# NVME.net
KiCad netlist of a schematic drawn in Altium Designer
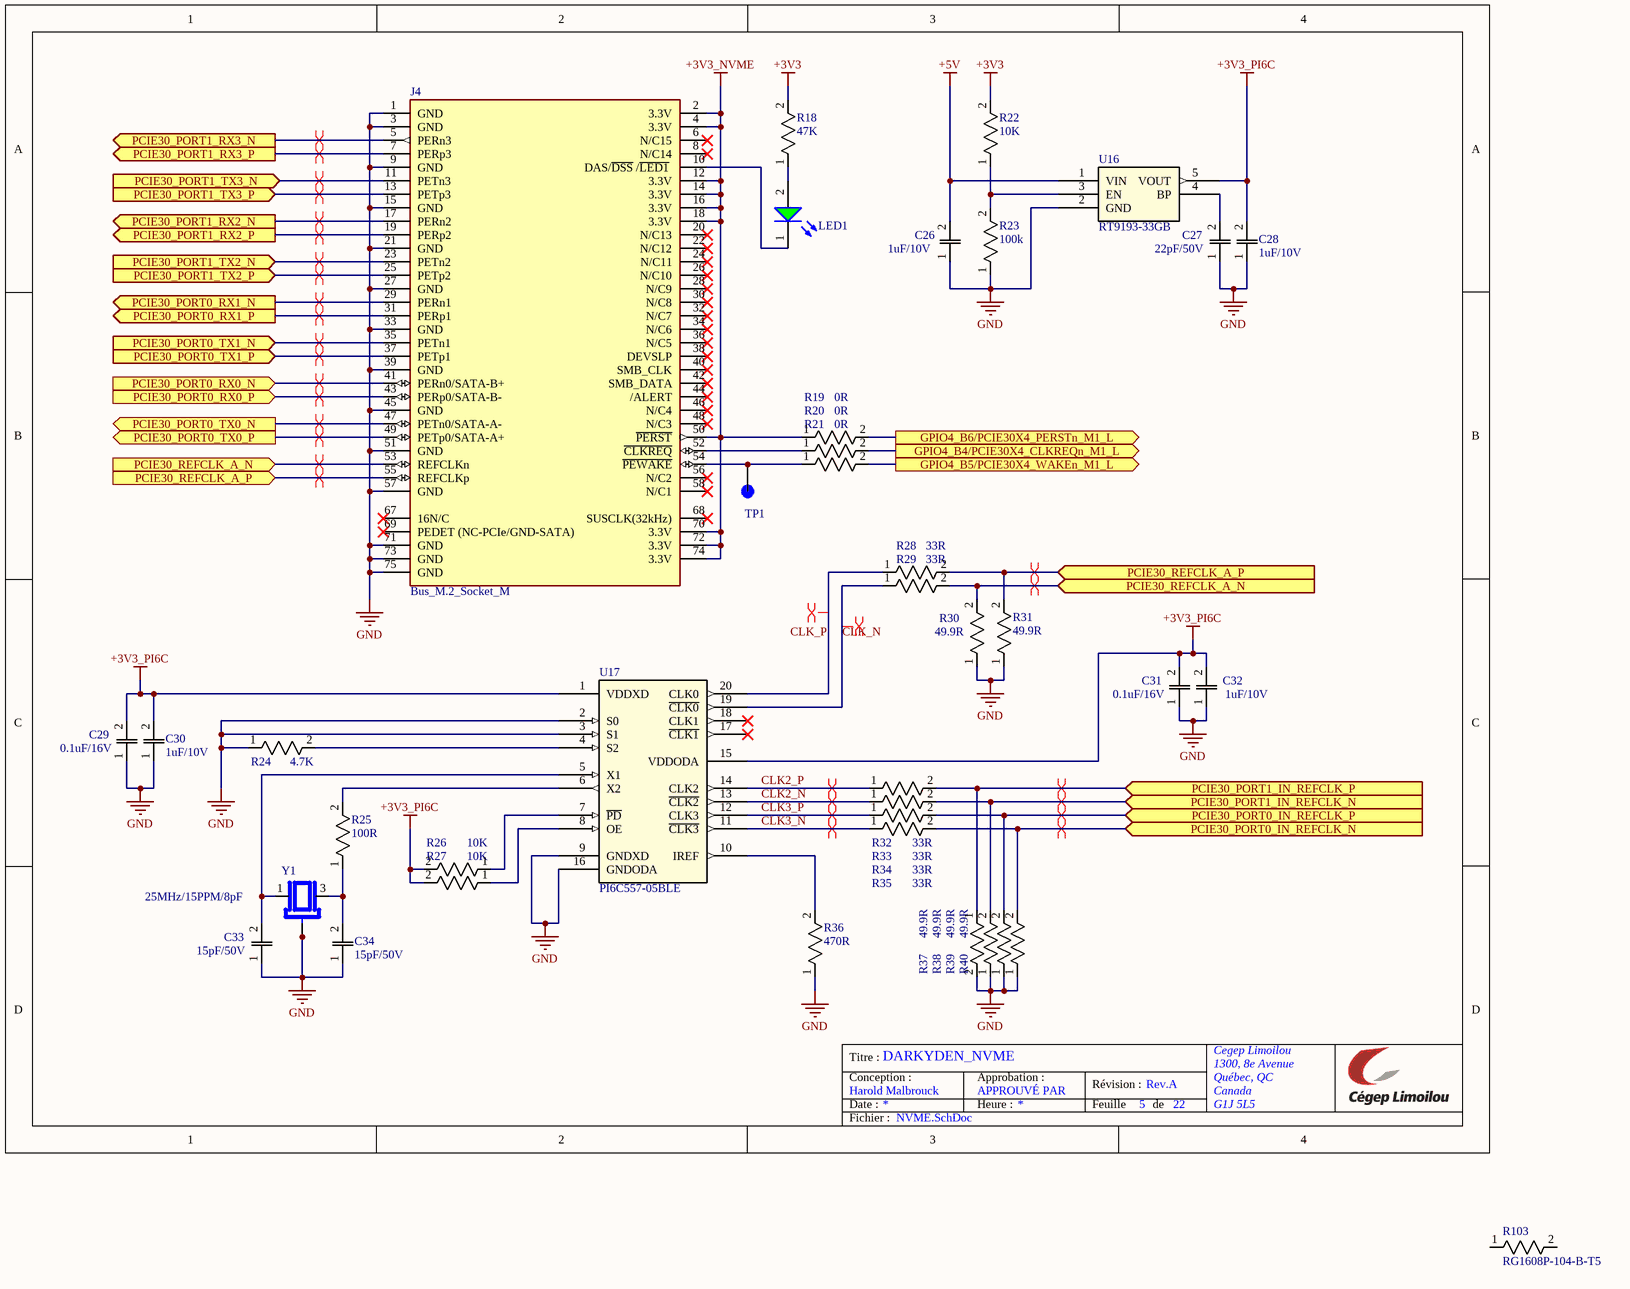
[diagram p0: NVME.SchDoc]

(export (version "E")
  (design (tool "Eeschema 10.0.6"))
  (components
    (comp (ref "C26")
      (value "1uF/10V")
      (footprint "CAPC220145_88N_KEM")
      (description "Multilayer Ceramic Capacitors MLCC - SMD/SMT 10V 1uF X7R 0805 10%")
      (fields
        (field (name "MANUFACTURER") "KEMET")
        (field (name "MANUFACTURER PART NUMBER") "C0805C105K8RACTU")
      )
      (libsource (lib "C0805C105K8RACTU") (part "C0805C105K8RACTU"))
    )
    (comp (ref "C27")
      (value "22pF/50V")
      (footprint "CAPC220145_88N_KEM")
      (description "Cap Ceramic 22pF 50V X7R 5% Pad SMD 0805 125°C T/R")
      (fields
        (field (name "MANUFACTURER") "KEMET")
        (field (name "MANUFACTURER PART NUMBER") "C0805C220J5RACTU")
      )
      (libsource (lib "C0805C220J5RACTU") (part "C0805C220J5RACTU"))
    )
    (comp (ref "C28")
      (value "1uF/10V")
      (footprint "CAPC220145_88N_KEM")
      (description "Multilayer Ceramic Capacitors MLCC - SMD/SMT 10V 1uF X7R 0805 10%")
      (fields
        (field (name "MANUFACTURER") "KEMET")
        (field (name "MANUFACTURER PART NUMBER") "C0805C105K8RACTU")
      )
      (libsource (lib "C0805C105K8RACTU") (part "C0805C105K8RACTU"))
    )
    (comp (ref "C29")
      (value "0.1uF/16V")
      (footprint "CAPC220145_88N_KEM")
      (description "0.1uF/16V ±10% X7R 0805 (2012METRIC) Ceramic Capacitor SMD Auto X7R")
      (fields
        (field (name "MANUFACTURER") "KEMET")
        (field (name "MANUFACTURER PART NUMBER") "C0805C104K4RACAUTO")
      )
      (libsource (lib "C0805C104K4RACAUTO") (part "C0805C104K4RACAUTO"))
    )
    (comp (ref "C30")
      (value "1uF/10V")
      (footprint "CAPC220145_88N_KEM")
      (description "Multilayer Ceramic Capacitors MLCC - SMD/SMT 10V 1uF X7R 0805 10%")
      (fields
        (field (name "MANUFACTURER") "KEMET")
        (field (name "MANUFACTURER PART NUMBER") "C0805C105K8RACTU")
      )
      (libsource (lib "C0805C105K8RACTU") (part "C0805C105K8RACTU"))
    )
    (comp (ref "C31")
      (value "0.1uF/16V")
      (footprint "CAPC220145_88N_KEM")
      (description "0.1uF/16V ±10% X7R 0805 (2012METRIC) Ceramic Capacitor SMD Auto X7R")
      (fields
        (field (name "MANUFACTURER") "KEMET")
        (field (name "MANUFACTURER PART NUMBER") "C0805C104K4RACAUTO")
      )
      (libsource (lib "C0805C104K4RACAUTO") (part "C0805C104K4RACAUTO"))
    )
    (comp (ref "C32")
      (value "1uF/10V")
      (footprint "CAPC220145_88N_KEM")
      (description "Multilayer Ceramic Capacitors MLCC - SMD/SMT 10V 1uF X7R 0805 10%")
      (fields
        (field (name "MANUFACTURER") "KEMET")
        (field (name "MANUFACTURER PART NUMBER") "C0805C105K8RACTU")
      )
      (libsource (lib "C0805C105K8RACTU") (part "C0805C105K8RACTU"))
    )
    (comp (ref "C33")
      (value "15pF/50V")
      (footprint "CAPC220145_88N_KEM")
      (description "Multilayer Ceramic Capacitors MLCC - SMD/SMT 50V 15pF X7R 0805 10% AEC-Q200")
      (fields
        (field (name "MANUFACTURER") "KEMET")
        (field (name "MANUFACTURER PART NUMBER") "C0805C150K5RACAUTO")
      )
      (libsource (lib "C0805C150K5RACAUTO") (part "C0805C150K5RACAUTO"))
    )
    (comp (ref "C34")
      (value "15pF/50V")
      (footprint "CAPC220145_88N_KEM")
      (description "Multilayer Ceramic Capacitors MLCC - SMD/SMT 50V 15pF X7R 0805 10% AEC-Q200")
      (fields
        (field (name "MANUFACTURER") "KEMET")
        (field (name "MANUFACTURER PART NUMBER") "C0805C150K5RACAUTO")
      )
      (libsource (lib "C0805C150K5RACAUTO") (part "C0805C150K5RACAUTO"))
    )
    (comp (ref "J4")
      (value "Bus_M.2_Socket_M")
      (footprint "AMPHENOL_MDT420M03001")
      (fields (field (name "MF") "Amphenol Commercial") (field (name "MP") "MDT420M03001"))
      (libsource (lib "Bus_M.2_Socket_M") (part "Bus_M.2_Socket_M"))
    )
    (comp (ref "LED1")
      (value "Green, 3.2V, 140°")
      (footprint "WL-SMCD_0603")
      (description "WL-SMCD Mono-color Chip LED Diffused, SMT, size 0603, Green, 3.2V, 140°")
      (fields
        (field (name "MANUFACTURER PART NUMBER") "150060GS55040")
        (field (name "MANUFACTURER") "Wurth Elektronik")
      )
      (libsource (lib "0603_LED") (part "GREEN"))
    )
    (comp (ref "R18")
      (value "47K")
      (footprint "RC0603N_PAN")
      (description "Resistor Thick Film 0603 47K Ohm 5% 1/10W 200ppm/C Molded SMD Punched Carrier T/R")
      (fields
        (field (name "MANUFACTURER") "Panasonic")
        (field (name "MANUFACTURER PART NUMBER") "ERJ-3GEYJ473V")
      )
      (libsource (lib "ERJ-3GEYJ473V") (part "ERJ-3GEYJ473V"))
    )
    (comp (ref "R19")
      (value "0R")
      (footprint "SamacSys:ERJ3EKF1000V")
      (description "Zero Ohm Resistor, Jumper, 0603 [1608 Metric], Thick Film, 100 mW, 1 A, Surface Mount")
      (fields
        (field (name "MANUFACTURER_PART_NUMBER") "ERJ-3GEY0R00V")
        (field (name "MOUSER PART NUMBER") "667-ERJ-3GEY0R00V")
      )
      (libsource (lib "SamacSys") (part "ERJ-3GEY0R00V"))
    )
    (comp (ref "R20")
      (value "0R")
      (footprint "SamacSys:ERJ3EKF1000V")
      (description "Zero Ohm Resistor, Jumper, 0603 [1608 Metric], Thick Film, 100 mW, 1 A, Surface Mount")
      (fields
        (field (name "MANUFACTURER_PART_NUMBER") "ERJ-3GEY0R00V")
        (field (name "MOUSER PART NUMBER") "667-ERJ-3GEY0R00V")
      )
      (libsource (lib "SamacSys") (part "ERJ-3GEY0R00V"))
    )
    (comp (ref "R21")
      (value "0R")
      (footprint "SamacSys:ERJ3EKF1000V")
      (description "Zero Ohm Resistor, Jumper, 0603 [1608 Metric], Thick Film, 100 mW, 1 A, Surface Mount")
      (fields
        (field (name "MANUFACTURER_PART_NUMBER") "ERJ-3GEY0R00V")
        (field (name "MOUSER PART NUMBER") "667-ERJ-3GEY0R00V")
      )
      (libsource (lib "SamacSys") (part "ERJ-3GEY0R00V"))
    )
    (comp (ref "R22")
      (value "10K")
      (footprint "SamacSys:ERJ3EKF1000V")
      (description "10K Ohm 5% Res Thick Film 0603  0.1W(1/10W) ±200ppm/C Pad SMD Automotive T/R")
      (fields
        (field (name "MANUFACTURER_PART_NUMBER") "ERJ-3GEYJ103V")
        (field (name "MOUSER PART NUMBER") "667-ERJ-3GEYJ103V")
      )
      (libsource (lib "SamacSys") (part "ERJ-3GEYJ103V"))
    )
    (comp (ref "R23")
      (value "100k")
      (footprint "SamacSys:ERJ3EKF1000V")
      (description "100K Ohm 5%  Res Thick Film 0603 1/10W +/-200ppm/ßC Molded SMD Punched Carrier T/R")
      (fields
        (field (name "MANUFACTURER_PART_NUMBER") "ERJ-3GEYJ104V")
        (field (name "MOUSER PART NUMBER") "667-ERJ-3GEYJ104V")
      )
      (libsource (lib "SamacSys") (part "ERJ-3GEYJ104V"))
    )
    (comp (ref "R24")
      (value "4.7K")
      (footprint "RC0603N_PAN")
      (description "Res Thin Film 0603 4.7K Ohm 0.1% 0.1W ±25ppm/°C Molded SMD Punched Carrier T/R")
      (fields
        (field (name "MANUFACTURER") "Panasonic")
        (field (name "MANUFACTURER PART NUMBER") "ERA-3AEB472V")
      )
      (libsource (lib "ERA-3AEB472V") (part "ERA-3AEB472V"))
    )
    (comp (ref "R25")
      (value "100R")
      (footprint "SamacSys:RESC1608X55N")
      (description "100 Ohm 1% 1/10W 0603 ±100ppm/°C Molded SMD Punched Carrier T/R")
      (fields
        (field (name "MANUFACTURER_PART_NUMBER") "ERJ-3EKF1000V")
        (field (name "MOUSER PART NUMBER") "667-ERJ-3EKF1000V")
      )
      (libsource (lib "SamacSys") (part "ERJ-3EKF1000V"))
    )
    (comp (ref "R26")
      (value "10K")
      (footprint "SamacSys:ERJ3EKF1000V")
      (description "10K Ohm 5% Res Thick Film 0603  0.1W(1/10W) ±200ppm/C Pad SMD Automotive T/R")
      (fields
        (field (name "MANUFACTURER_PART_NUMBER") "ERJ-3GEYJ103V")
        (field (name "MOUSER PART NUMBER") "667-ERJ-3GEYJ103V")
      )
      (libsource (lib "SamacSys") (part "ERJ-3GEYJ103V"))
    )
    (comp (ref "R27")
      (value "10K")
      (footprint "SamacSys:ERJ3EKF1000V")
      (description "10K Ohm 5% Res Thick Film 0603  0.1W(1/10W) ±200ppm/C Pad SMD Automotive T/R")
      (fields
        (field (name "MANUFACTURER_PART_NUMBER") "ERJ-3GEYJ103V")
        (field (name "MOUSER PART NUMBER") "667-ERJ-3GEYJ103V")
      )
      (libsource (lib "SamacSys") (part "ERJ-3GEYJ103V"))
    )
    (comp (ref "R28")
      (value "33R")
      (footprint "RC0603N_PAN")
      (description "Res Thick Film 0603 33 Ohm 1% 0.1W ±100ppm/°C Molded SMD Punched Carrier T/R")
      (fields
        (field (name "MANUFACTURER") "Panasonic")
        (field (name "MANUFACTURER PART NUMBER") "ERJ-3EKF33R0V")
      )
      (libsource (lib "ERJ-3EKF33R0V") (part "ERJ-3EKF33R0V"))
    )
    (comp (ref "R29")
      (value "33R")
      (footprint "RC0603N_PAN")
      (description "Res Thick Film 0603 33 Ohm 1% 0.1W ±100ppm/°C Molded SMD Punched Carrier T/R")
      (fields
        (field (name "MANUFACTURER") "Panasonic")
        (field (name "MANUFACTURER PART NUMBER") "ERJ-3EKF33R0V")
      )
      (libsource (lib "ERJ-3EKF33R0V") (part "ERJ-3EKF33R0V"))
    )
    (comp (ref "R30")
      (value "49.9R")
      (footprint "RC0603N_PAN")
      (description "100Mw Thick Film Resistors 100Ppm/ 1% 49.9 0603 Chip Resistor Surface Mount Rohs")
      (fields
        (field (name "MANUFACTURER") "Panasonic")
        (field (name "MANUFACTURER PART NUMBER") "ERJ-3EKF49R9V")
      )
      (libsource (lib "ERJ-3EKF49R9V") (part "ERJ-3EKF49R9V"))
    )
    (comp (ref "R31")
      (value "49.9R")
      (footprint "RC0603N_PAN")
      (description "100Mw Thick Film Resistors 100Ppm/ 1% 49.9 0603 Chip Resistor Surface Mount Rohs")
      (fields
        (field (name "MANUFACTURER") "Panasonic")
        (field (name "MANUFACTURER PART NUMBER") "ERJ-3EKF49R9V")
      )
      (libsource (lib "ERJ-3EKF49R9V") (part "ERJ-3EKF49R9V"))
    )
    (comp (ref "R32")
      (value "33R")
      (footprint "RC0603N_PAN")
      (description "Res Thick Film 0603 33 Ohm 1% 0.1W ±100ppm/°C Molded SMD Punched Carrier T/R")
      (fields
        (field (name "MANUFACTURER") "Panasonic")
        (field (name "MANUFACTURER PART NUMBER") "ERJ-3EKF33R0V")
      )
      (libsource (lib "ERJ-3EKF33R0V") (part "ERJ-3EKF33R0V"))
    )
    (comp (ref "R33")
      (value "33R")
      (footprint "RC0603N_PAN")
      (description "Res Thick Film 0603 33 Ohm 1% 0.1W ±100ppm/°C Molded SMD Punched Carrier T/R")
      (fields
        (field (name "MANUFACTURER") "Panasonic")
        (field (name "MANUFACTURER PART NUMBER") "ERJ-3EKF33R0V")
      )
      (libsource (lib "ERJ-3EKF33R0V") (part "ERJ-3EKF33R0V"))
    )
    (comp (ref "R34")
      (value "33R")
      (footprint "RC0603N_PAN")
      (description "Res Thick Film 0603 33 Ohm 1% 0.1W ±100ppm/°C Molded SMD Punched Carrier T/R")
      (fields
        (field (name "MANUFACTURER") "Panasonic")
        (field (name "MANUFACTURER PART NUMBER") "ERJ-3EKF33R0V")
      )
      (libsource (lib "ERJ-3EKF33R0V") (part "ERJ-3EKF33R0V"))
    )
    (comp (ref "R35")
      (value "33R")
      (footprint "RC0603N_PAN")
      (description "Res Thick Film 0603 33 Ohm 1% 0.1W ±100ppm/°C Molded SMD Punched Carrier T/R")
      (fields
        (field (name "MANUFACTURER") "Panasonic")
        (field (name "MANUFACTURER PART NUMBER") "ERJ-3EKF33R0V")
      )
      (libsource (lib "ERJ-3EKF33R0V") (part "ERJ-3EKF33R0V"))
    )
    (comp (ref "R36")
      (value "470R")
      (footprint "RC0603N_PAN")
      (description "Res Thick Film 0603 470 Ohm 5% 1/10W +/-200ppm/ßC Molded SMD Punched Carrier T/R")
      (fields
        (field (name "MANUFACTURER") "Panasonic")
        (field (name "MANUFACTURER PART NUMBER") "ERJ-3GEYJ471V")
      )
      (libsource (lib "ERJ-3GEYJ471V") (part "ERJ-3GEYJ471V"))
    )
    (comp (ref "R37")
      (value "49.9R")
      (footprint "RC0603N_PAN")
      (description "100Mw Thick Film Resistors 100Ppm/ 1% 49.9 0603 Chip Resistor Surface Mount Rohs")
      (fields
        (field (name "MANUFACTURER") "Panasonic")
        (field (name "MANUFACTURER PART NUMBER") "ERJ-3EKF49R9V")
      )
      (libsource (lib "ERJ-3EKF49R9V") (part "ERJ-3EKF49R9V"))
    )
    (comp (ref "R38")
      (value "49.9R")
      (footprint "RC0603N_PAN")
      (description "100Mw Thick Film Resistors 100Ppm/ 1% 49.9 0603 Chip Resistor Surface Mount Rohs")
      (fields
        (field (name "MANUFACTURER") "Panasonic")
        (field (name "MANUFACTURER PART NUMBER") "ERJ-3EKF49R9V")
      )
      (libsource (lib "ERJ-3EKF49R9V") (part "ERJ-3EKF49R9V"))
    )
    (comp (ref "R39")
      (value "49.9R")
      (footprint "RC0603N_PAN")
      (description "100Mw Thick Film Resistors 100Ppm/ 1% 49.9 0603 Chip Resistor Surface Mount Rohs")
      (fields
        (field (name "MANUFACTURER") "Panasonic")
        (field (name "MANUFACTURER PART NUMBER") "ERJ-3EKF49R9V")
      )
      (libsource (lib "ERJ-3EKF49R9V") (part "ERJ-3EKF49R9V"))
    )
    (comp (ref "R40")
      (value "49.9R")
      (footprint "RC0603N_PAN")
      (description "100Mw Thick Film Resistors 100Ppm/ 1% 49.9 0603 Chip Resistor Surface Mount Rohs")
      (fields
        (field (name "MANUFACTURER") "Panasonic")
        (field (name "MANUFACTURER PART NUMBER") "ERJ-3EKF49R9V")
      )
      (libsource (lib "ERJ-3EKF49R9V") (part "ERJ-3EKF49R9V"))
    )
    (comp (ref "R103")
      (value "RG1608P-104-B-T5")
      (footprint "RES_0816_SUS")
      (description "No Description Available")
      (libsource (lib "RES_SMD_0603") (part "RG1608P-104-B-T5"))
    )
    (comp (ref "TP1")
      (value "5006")
      (footprint "KEYSTONE_5006")
      (description "Test Point Compact THM PC .350 L .125 OD Heat Resistant Nylon 46 Black ¦ Keystone Electronics 5006")
      (fields (field (name "MF") "Keystone Electronics Corp."))
      (libsource (lib "test_point") (part "5006"))
    )
    (comp (ref "U16")
      (value "RT9193-33GB")
      (footprint "SOT-23-5_RIT")
      (description "RT9193 Series 300 mA 3.3 V Ultra-Low Noise Ultra-Fast CMOS LDO Regulator-SC-70-5")
      (fields (field (name "MANUFACTURER") "Richtek"))
      (libsource (lib "RT9193-33GB") (part "RT9193-33GB"))
    )
    (comp (ref "U17")
      (value "PI6C557-05BLE")
      (footprint "L20_PER-M")
      (description "Clock Generators & Support Products PCI express Gen 2 4 output clock gen")
      (fields (field (name "MANUFACTURER") "Diodes"))
      (libsource (lib "PI6C557-05BLE") (part "PI6C557-05BLE"))
    )
    (comp (ref "Y1")
      (value "25MHz/15PPM/8pF")
      (footprint "XTAL_ECS-250-8-37B2-RWY-TR")
      (description "Crystal 25MHz ±15ppm (Tol) ±15ppm (Stability) 8pF FUND 50Ohm 4-Pin Mini-CSMD T/R")
      (fields (field (name "MF") "{'manufacturer': u'ECS Inc.'}") (field (name "MP") "ECS-250-8-37B2-RWY-TR"))
      (libsource (lib "ECS-250-8-37B2-RWY-TR") (part "ECS-250-8-37B2-RWY-TR"))
    )
  )
  (nets
    (net (code "1") (name "+3V3") (class "Default")
      (node (ref "R18") (pin "2") (pinfunction "2_2") (pintype "passive"))
      (node (ref "R22") (pin "2") (pinfunction "2_2") (pintype "passive"))
    )
    (net (code "2") (name "+3V3_NVME") (class "Default")
      (node (ref "J4") (pin "12") (pinfunction "3.3V_12") (pintype "power_in"))
      (node (ref "J4") (pin "14") (pinfunction "3.3V_14") (pintype "power_in"))
      (node (ref "J4") (pin "16") (pinfunction "3.3V_16") (pintype "power_in"))
      (node (ref "J4") (pin "18") (pinfunction "3.3V_18") (pintype "power_in"))
      (node (ref "J4") (pin "2") (pinfunction "3.3V_2") (pintype "power_in"))
      (node (ref "J4") (pin "4") (pinfunction "3.3V_4") (pintype "power_in"))
      (node (ref "J4") (pin "50") (pinfunction "~{PERST}_50") (pintype "output"))
      (node (ref "J4") (pin "70") (pinfunction "3.3V_70") (pintype "power_in"))
      (node (ref "J4") (pin "72") (pinfunction "3.3V_72") (pintype "power_in"))
      (node (ref "J4") (pin "74") (pinfunction "3.3V_74") (pintype "power_in"))
      (node (ref "R19") (pin "1") (pinfunction "1_1") (pintype "passive"))
    )
    (net (code "3") (name "+3V3_PI6C") (class "Default")
      (node (ref "C28") (pin "2") (pinfunction "2_2") (pintype "passive"))
      (node (ref "C29") (pin "2") (pinfunction "2_2") (pintype "passive"))
      (node (ref "C30") (pin "2") (pinfunction "2_2") (pintype "passive"))
      (node (ref "C31") (pin "2") (pinfunction "2_2") (pintype "passive"))
      (node (ref "C32") (pin "2") (pinfunction "2_2") (pintype "passive"))
      (node (ref "R26") (pin "2") (pinfunction "2_2") (pintype "passive"))
      (node (ref "R27") (pin "2") (pinfunction "2_2") (pintype "passive"))
      (node (ref "U16") (pin "5") (pinfunction "VOUT_5") (pintype "output"))
      (node (ref "U17") (pin "1") (pinfunction "VDDXD_1") (pintype "power_in"))
      (node (ref "U17") (pin "15") (pinfunction "VDDODA_15") (pintype "power_in"))
    )
    (net (code "4") (name "+5V") (class "Default")
      (node (ref "C26") (pin "2") (pinfunction "2_2") (pintype "passive"))
      (node (ref "U16") (pin "1") (pinfunction "VIN_1") (pintype "power_in"))
    )
    (net (code "5") (name "/CLK2_N") (class "Default")
      (node (ref "R33") (pin "1") (pinfunction "1_1") (pintype "passive"))
      (node (ref "U17") (pin "13") (pinfunction "~{CLK2}_13") (pintype "output"))
    )
    (net (code "6") (name "/CLK2_P") (class "Default")
      (node (ref "R32") (pin "1") (pinfunction "1_1") (pintype "passive"))
      (node (ref "U17") (pin "14") (pinfunction "CLK2_14") (pintype "output"))
    )
    (net (code "7") (name "/CLK3_N") (class "Default")
      (node (ref "R35") (pin "1") (pinfunction "1_1") (pintype "passive"))
      (node (ref "U17") (pin "11") (pinfunction "~{CLK3}_11") (pintype "output"))
    )
    (net (code "8") (name "/CLK3_P") (class "Default")
      (node (ref "R34") (pin "1") (pinfunction "1_1") (pintype "passive"))
      (node (ref "U17") (pin "12") (pinfunction "CLK3_12") (pintype "output"))
    )
    (net (code "9") (name "/CLK_N") (class "Default")
      (node (ref "R29") (pin "1") (pinfunction "1_1") (pintype "passive"))
      (node (ref "U17") (pin "19") (pinfunction "~{CLK0}_19") (pintype "output"))
    )
    (net (code "10") (name "/CLK_P") (class "Default")
      (node (ref "R28") (pin "1") (pinfunction "1_1") (pintype "passive"))
      (node (ref "U17") (pin "20") (pinfunction "CLK0_20") (pintype "output"))
    )
    (net (code "11") (name "/GPIO4_B4{slash}PCIE30X4_CLKREQn_M1_L") (class "Default")
      (node (ref "R20") (pin "2") (pinfunction "2_2") (pintype "passive"))
    )
    (net (code "12") (name "/GPIO4_B5{slash}PCIE30X4_WAKEn_M1_L") (class "Default")
      (node (ref "R21") (pin "2") (pinfunction "2_2") (pintype "passive"))
    )
    (net (code "13") (name "/GPIO4_B6{slash}PCIE30X4_PERSTn_M1_L") (class "Default")
      (node (ref "R19") (pin "2") (pinfunction "2_2") (pintype "passive"))
    )
    (net (code "14") (name "/PCIE30_PORT0_IN_REFCLK_N") (class "Default")
      (node (ref "R35") (pin "2") (pinfunction "2_2") (pintype "passive"))
      (node (ref "R40") (pin "2") (pinfunction "2_2") (pintype "passive"))
    )
    (net (code "15") (name "/PCIE30_PORT0_IN_REFCLK_P") (class "Default")
      (node (ref "R34") (pin "2") (pinfunction "2_2") (pintype "passive"))
      (node (ref "R39") (pin "2") (pinfunction "2_2") (pintype "passive"))
    )
    (net (code "16") (name "/PCIE30_PORT0_RX0_N") (class "Default")
      (node (ref "J4") (pin "41") (pinfunction "PERn0/SATA-B+_41") (pintype "bidirectional"))
    )
    (net (code "17") (name "/PCIE30_PORT0_RX0_P") (class "Default")
      (node (ref "J4") (pin "43") (pinfunction "PERp0/SATA-B-_43") (pintype "bidirectional"))
    )
    (net (code "18") (name "/PCIE30_PORT0_RX1_N") (class "Default")
      (node (ref "J4") (pin "29") (pinfunction "PERn1_29") (pintype "passive"))
    )
    (net (code "19") (name "/PCIE30_PORT0_RX1_P") (class "Default")
      (node (ref "J4") (pin "31") (pinfunction "PERp1_31") (pintype "passive"))
    )
    (net (code "20") (name "/PCIE30_PORT0_TX0_N") (class "Default")
      (node (ref "J4") (pin "47") (pinfunction "PETn0/SATA-A-_47") (pintype "bidirectional"))
    )
    (net (code "21") (name "/PCIE30_PORT0_TX0_P") (class "Default")
      (node (ref "J4") (pin "49") (pinfunction "PETp0/SATA-A+_49") (pintype "bidirectional"))
    )
    (net (code "22") (name "/PCIE30_PORT0_TX1_N") (class "Default")
      (node (ref "J4") (pin "35") (pinfunction "PETn1_35") (pintype "passive"))
    )
    (net (code "23") (name "/PCIE30_PORT0_TX1_P") (class "Default")
      (node (ref "J4") (pin "37") (pinfunction "PETp1_37") (pintype "passive"))
    )
    (net (code "24") (name "/PCIE30_PORT1_IN_REFCLK_N") (class "Default")
      (node (ref "R33") (pin "2") (pinfunction "2_2") (pintype "passive"))
      (node (ref "R38") (pin "2") (pinfunction "2_2") (pintype "passive"))
    )
    (net (code "25") (name "/PCIE30_PORT1_IN_REFCLK_P") (class "Default")
      (node (ref "R32") (pin "2") (pinfunction "2_2") (pintype "passive"))
      (node (ref "R37") (pin "1") (pinfunction "1_1") (pintype "passive"))
    )
    (net (code "26") (name "/PCIE30_PORT1_RX2_N") (class "Default")
      (node (ref "J4") (pin "17") (pinfunction "PERn2_17") (pintype "passive"))
    )
    (net (code "27") (name "/PCIE30_PORT1_RX2_P") (class "Default")
      (node (ref "J4") (pin "19") (pinfunction "PERp2_19") (pintype "passive"))
    )
    (net (code "28") (name "/PCIE30_PORT1_RX3_N") (class "Default")
      (node (ref "J4") (pin "5") (pinfunction "PERn3_5") (pintype "output"))
    )
    (net (code "29") (name "/PCIE30_PORT1_RX3_P") (class "Default")
      (node (ref "J4") (pin "7") (pinfunction "PERp3_7") (pintype "passive"))
    )
    (net (code "30") (name "/PCIE30_PORT1_TX2_N") (class "Default")
      (node (ref "J4") (pin "23") (pinfunction "PETn2_23") (pintype "passive"))
    )
    (net (code "31") (name "/PCIE30_PORT1_TX2_P") (class "Default")
      (node (ref "J4") (pin "25") (pinfunction "PETp2_25") (pintype "passive"))
    )
    (net (code "32") (name "/PCIE30_PORT1_TX3_N") (class "Default")
      (node (ref "J4") (pin "11") (pinfunction "PETn3_11") (pintype "passive"))
    )
    (net (code "33") (name "/PCIE30_PORT1_TX3_P") (class "Default")
      (node (ref "J4") (pin "13") (pinfunction "PETp3_13") (pintype "passive"))
    )
    (net (code "34") (name "/PCIE30_REFCLK_A_N") (class "Default")
      (node (ref "J4") (pin "53") (pinfunction "REFCLKn_53") (pintype "bidirectional"))
      (node (ref "R29") (pin "2") (pinfunction "2_2") (pintype "passive"))
      (node (ref "R30") (pin "2") (pinfunction "2_2") (pintype "passive"))
    )
    (net (code "35") (name "/PCIE30_REFCLK_A_P") (class "Default")
      (node (ref "J4") (pin "55") (pinfunction "REFCLKp_55") (pintype "bidirectional"))
      (node (ref "R28") (pin "2") (pinfunction "2_2") (pintype "passive"))
      (node (ref "R31") (pin "2") (pinfunction "2_2") (pintype "passive"))
    )
    (net (code "36") (name "GND") (class "Default")
      (node (ref "C26") (pin "1") (pinfunction "1_1") (pintype "passive"))
      (node (ref "C27") (pin "1") (pinfunction "1_1") (pintype "passive"))
      (node (ref "C28") (pin "1") (pinfunction "1_1") (pintype "passive"))
      (node (ref "C29") (pin "1") (pinfunction "1_1") (pintype "passive"))
      (node (ref "C30") (pin "1") (pinfunction "1_1") (pintype "passive"))
      (node (ref "C31") (pin "1") (pinfunction "1_1") (pintype "passive"))
      (node (ref "C32") (pin "1") (pinfunction "1_1") (pintype "passive"))
      (node (ref "C33") (pin "1") (pinfunction "1_1") (pintype "passive"))
      (node (ref "C34") (pin "1") (pinfunction "1_1") (pintype "passive"))
      (node (ref "J4") (pin "1") (pinfunction "GND_1") (pintype "passive"))
      (node (ref "J4") (pin "15") (pinfunction "GND_15") (pintype "passive"))
      (node (ref "J4") (pin "21") (pinfunction "GND_21") (pintype "passive"))
      (node (ref "J4") (pin "27") (pinfunction "GND_27") (pintype "passive"))
      (node (ref "J4") (pin "3") (pinfunction "GND_3") (pintype "passive"))
      (node (ref "J4") (pin "33") (pinfunction "GND_33") (pintype "passive"))
      (node (ref "J4") (pin "39") (pinfunction "GND_39") (pintype "passive"))
      (node (ref "J4") (pin "45") (pinfunction "GND_45") (pintype "passive"))
      (node (ref "J4") (pin "51") (pinfunction "GND_51") (pintype "passive"))
      (node (ref "J4") (pin "57") (pinfunction "GND_57") (pintype "passive"))
      (node (ref "J4") (pin "71") (pinfunction "GND_71") (pintype "passive"))
      (node (ref "J4") (pin "73") (pinfunction "GND_73") (pintype "passive"))
      (node (ref "J4") (pin "75") (pinfunction "GND_75") (pintype "passive"))
      (node (ref "J4") (pin "9") (pinfunction "GND_9") (pintype "passive"))
      (node (ref "R23") (pin "1") (pinfunction "1_1") (pintype "passive"))
      (node (ref "R24") (pin "1") (pinfunction "1_1") (pintype "passive"))
      (node (ref "R30") (pin "1") (pinfunction "1_1") (pintype "passive"))
      (node (ref "R31") (pin "1") (pinfunction "1_1") (pintype "passive"))
      (node (ref "R36") (pin "1") (pinfunction "1_1") (pintype "passive"))
      (node (ref "R37") (pin "2") (pinfunction "2_2") (pintype "passive"))
      (node (ref "R38") (pin "1") (pinfunction "1_1") (pintype "passive"))
      (node (ref "R39") (pin "1") (pinfunction "1_1") (pintype "passive"))
      (node (ref "R40") (pin "1") (pinfunction "1_1") (pintype "passive"))
      (node (ref "U16") (pin "2") (pinfunction "GND_2") (pintype "passive"))
      (node (ref "U17") (pin "16") (pinfunction "GNDODA_16") (pintype "passive"))
      (node (ref "U17") (pin "2") (pinfunction "S0_2") (pintype "input"))
      (node (ref "U17") (pin "3") (pinfunction "S1_3") (pintype "input"))
      (node (ref "U17") (pin "9") (pinfunction "GNDXD_9") (pintype "passive"))
      (node (ref "Y1") (pin "2") (pinfunction "GND_2") (pintype "power_in"))
      (node (ref "Y1") (pin "4") (pinfunction "GND_4") (pintype "power_in"))
    )
    (net (code "37") (name "Net-(J4-DAS{slash}~{DSS}_{slash}~{LED1})") (class "Default")
      (node (ref "J4") (pin "10") (pinfunction "DAS/~{DSS}_/~{LED1}_10") (pintype "passive"))
      (node (ref "LED1") (pin "1") (pinfunction "K_1") (pintype "passive"))
    )
    (net (code "38") (name "Net-(J4-~{CLKREQ})") (class "Default")
      (node (ref "J4") (pin "52") (pinfunction "~{CLKREQ}_52") (pintype "bidirectional"))
      (node (ref "R20") (pin "1") (pinfunction "1_1") (pintype "passive"))
    )
    (net (code "39") (name "Net-(J4-~{PEWAKE})") (class "Default")
      (node (ref "J4") (pin "54") (pinfunction "~{PEWAKE}_54") (pintype "bidirectional"))
      (node (ref "R21") (pin "1") (pinfunction "1_1") (pintype "passive"))
      (node (ref "TP1") (pin "TP") (pinfunction "TP_TP") (pintype "passive"))
    )
    (net (code "40") (name "Net-(LED1-A)") (class "Default")
      (node (ref "LED1") (pin "2") (pinfunction "A_2") (pintype "passive"))
      (node (ref "R18") (pin "1") (pinfunction "1_1") (pintype "passive"))
    )
    (net (code "41") (name "Net-(U16-BP)") (class "Default")
      (node (ref "C27") (pin "2") (pinfunction "2_2") (pintype "passive"))
      (node (ref "U16") (pin "4") (pinfunction "BP_4") (pintype "passive"))
    )
    (net (code "42") (name "Net-(U16-EN)") (class "Default")
      (node (ref "R22") (pin "1") (pinfunction "1_1") (pintype "passive"))
      (node (ref "R23") (pin "2") (pinfunction "2_2") (pintype "passive"))
      (node (ref "U16") (pin "3") (pinfunction "EN_3") (pintype "passive"))
    )
    (net (code "43") (name "Net-(U17-IREF)") (class "Default")
      (node (ref "R36") (pin "2") (pinfunction "2_2") (pintype "passive"))
      (node (ref "U17") (pin "10") (pinfunction "IREF_10") (pintype "output"))
    )
    (net (code "44") (name "Net-(U17-OE)") (class "Default")
      (node (ref "R27") (pin "1") (pinfunction "1_1") (pintype "passive"))
      (node (ref "U17") (pin "8") (pinfunction "OE_8") (pintype "input"))
    )
    (net (code "45") (name "Net-(U17-S2)") (class "Default")
      (node (ref "R24") (pin "2") (pinfunction "2_2") (pintype "passive"))
      (node (ref "U17") (pin "4") (pinfunction "S2_4") (pintype "input"))
    )
    (net (code "46") (name "Net-(U17-X1)") (class "Default")
      (node (ref "C33") (pin "2") (pinfunction "2_2") (pintype "passive"))
      (node (ref "U17") (pin "5") (pinfunction "X1_5") (pintype "input"))
      (node (ref "Y1") (pin "1") (pinfunction "IN/OUT_1") (pintype "passive"))
    )
    (net (code "47") (name "Net-(U17-X2)") (class "Default")
      (node (ref "R25") (pin "2") (pinfunction "2_2") (pintype "passive"))
      (node (ref "U17") (pin "6") (pinfunction "X2_6") (pintype "output"))
    )
    (net (code "48") (name "Net-(U17-~{PD})") (class "Default")
      (node (ref "R26") (pin "1") (pinfunction "1_1") (pintype "passive"))
      (node (ref "U17") (pin "7") (pinfunction "~{PD}_7") (pintype "input"))
    )
    (net (code "49") (name "Net-(Y1-OUT{slash}IN)") (class "Default")
      (node (ref "C34") (pin "2") (pinfunction "2_2") (pintype "passive"))
      (node (ref "R25") (pin "1") (pinfunction "1_1") (pintype "passive"))
      (node (ref "Y1") (pin "3") (pinfunction "OUT/IN_3") (pintype "passive"))
    )
    (net (code "50") (name "unconnected-(J4-16N{slash}C-Pad67)") (class "Default")
      (node (ref "J4") (pin "67") (pinfunction "16N/C_67") (pintype "passive+no_connect"))
    )
    (net (code "51") (name "unconnected-(J4-DEVSLP-Pad38)") (class "Default")
      (node (ref "J4") (pin "38") (pinfunction "DEVSLP_38") (pintype "passive+no_connect"))
    )
    (net (code "52") (name "unconnected-(J4-N{slash}C1-Pad58)") (class "Default")
      (node (ref "J4") (pin "58") (pinfunction "N/C1_58") (pintype "passive+no_connect"))
    )
    (net (code "53") (name "unconnected-(J4-N{slash}C2-Pad56)") (class "Default")
      (node (ref "J4") (pin "56") (pinfunction "N/C2_56") (pintype "passive+no_connect"))
    )
    (net (code "54") (name "unconnected-(J4-N{slash}C3-Pad48)") (class "Default")
      (node (ref "J4") (pin "48") (pinfunction "N/C3_48") (pintype "passive+no_connect"))
    )
    (net (code "55") (name "unconnected-(J4-N{slash}C4-Pad46)") (class "Default")
      (node (ref "J4") (pin "46") (pinfunction "N/C4_46") (pintype "passive+no_connect"))
    )
    (net (code "56") (name "unconnected-(J4-N{slash}C5-Pad36)") (class "Default")
      (node (ref "J4") (pin "36") (pinfunction "N/C5_36") (pintype "passive+no_connect"))
    )
    (net (code "57") (name "unconnected-(J4-N{slash}C6-Pad34)") (class "Default")
      (node (ref "J4") (pin "34") (pinfunction "N/C6_34") (pintype "passive+no_connect"))
    )
    (net (code "58") (name "unconnected-(J4-N{slash}C7-Pad32)") (class "Default")
      (node (ref "J4") (pin "32") (pinfunction "N/C7_32") (pintype "passive+no_connect"))
    )
    (net (code "59") (name "unconnected-(J4-N{slash}C8-Pad30)") (class "Default")
      (node (ref "J4") (pin "30") (pinfunction "N/C8_30") (pintype "passive+no_connect"))
    )
    (net (code "60") (name "unconnected-(J4-N{slash}C9-Pad28)") (class "Default")
      (node (ref "J4") (pin "28") (pinfunction "N/C9_28") (pintype "passive+no_connect"))
    )
    (net (code "61") (name "unconnected-(J4-N{slash}C10-Pad26)") (class "Default")
      (node (ref "J4") (pin "26") (pinfunction "N/C10_26") (pintype "passive+no_connect"))
    )
    (net (code "62") (name "unconnected-(J4-N{slash}C11-Pad24)") (class "Default")
      (node (ref "J4") (pin "24") (pinfunction "N/C11_24") (pintype "passive+no_connect"))
    )
    (net (code "63") (name "unconnected-(J4-N{slash}C12-Pad22)") (class "Default")
      (node (ref "J4") (pin "22") (pinfunction "N/C12_22") (pintype "passive+no_connect"))
    )
    (net (code "64") (name "unconnected-(J4-N{slash}C13-Pad20)") (class "Default")
      (node (ref "J4") (pin "20") (pinfunction "N/C13_20") (pintype "passive+no_connect"))
    )
    (net (code "65") (name "unconnected-(J4-N{slash}C14-Pad8)") (class "Default")
      (node (ref "J4") (pin "8") (pinfunction "N/C14_8") (pintype "passive+no_connect"))
    )
    (net (code "66") (name "unconnected-(J4-N{slash}C15-Pad6)") (class "Default")
      (node (ref "J4") (pin "6") (pinfunction "N/C15_6") (pintype "passive+no_connect"))
    )
    (net (code "67") (name "unconnected-(J4-PEDET_(NC-PCIe{slash}GND-SATA)-Pad69)") (class "Default")
      (node (ref "J4") (pin "69") (pinfunction "PEDET_(NC-PCIe/GND-SATA)_69") (pintype "passive+no_connect"))
    )
    (net (code "68") (name "unconnected-(J4-SMB_CLK-Pad40)") (class "Default")
      (node (ref "J4") (pin "40") (pinfunction "SMB_CLK_40") (pintype "passive+no_connect"))
    )
    (net (code "69") (name "unconnected-(J4-SMB_DATA-Pad42)") (class "Default")
      (node (ref "J4") (pin "42") (pinfunction "SMB_DATA_42") (pintype "passive+no_connect"))
    )
    (net (code "70") (name "unconnected-(J4-SUSCLK(32kHz)-Pad68)") (class "Default")
      (node (ref "J4") (pin "68") (pinfunction "SUSCLK(32kHz)_68") (pintype "passive+no_connect"))
    )
    (net (code "71") (name "unconnected-(J4-{slash}ALERT-Pad44)") (class "Default")
      (node (ref "J4") (pin "44") (pinfunction "/ALERT_44") (pintype "passive+no_connect"))
    )
    (net (code "72") (name "unconnected-(R103-Pad1)") (class "Default")
      (node (ref "R103") (pin "1") (pinfunction "1_1") (pintype "passive"))
    )
    (net (code "73") (name "unconnected-(R103-Pad2)") (class "Default")
      (node (ref "R103") (pin "2") (pinfunction "2_2") (pintype "passive"))
    )
    (net (code "74") (name "unconnected-(U17-CLK1-Pad18)") (class "Default")
      (node (ref "U17") (pin "18") (pinfunction "CLK1_18") (pintype "output+no_connect"))
    )
    (net (code "75") (name "unconnected-(U17-~{CLK1}-Pad17)") (class "Default")
      (node (ref "U17") (pin "17") (pinfunction "~{CLK1}_17") (pintype "output+no_connect"))
    )
  )
)
